# me433_2017.net
KiCad netlist of a schematic drawn in EAGLE
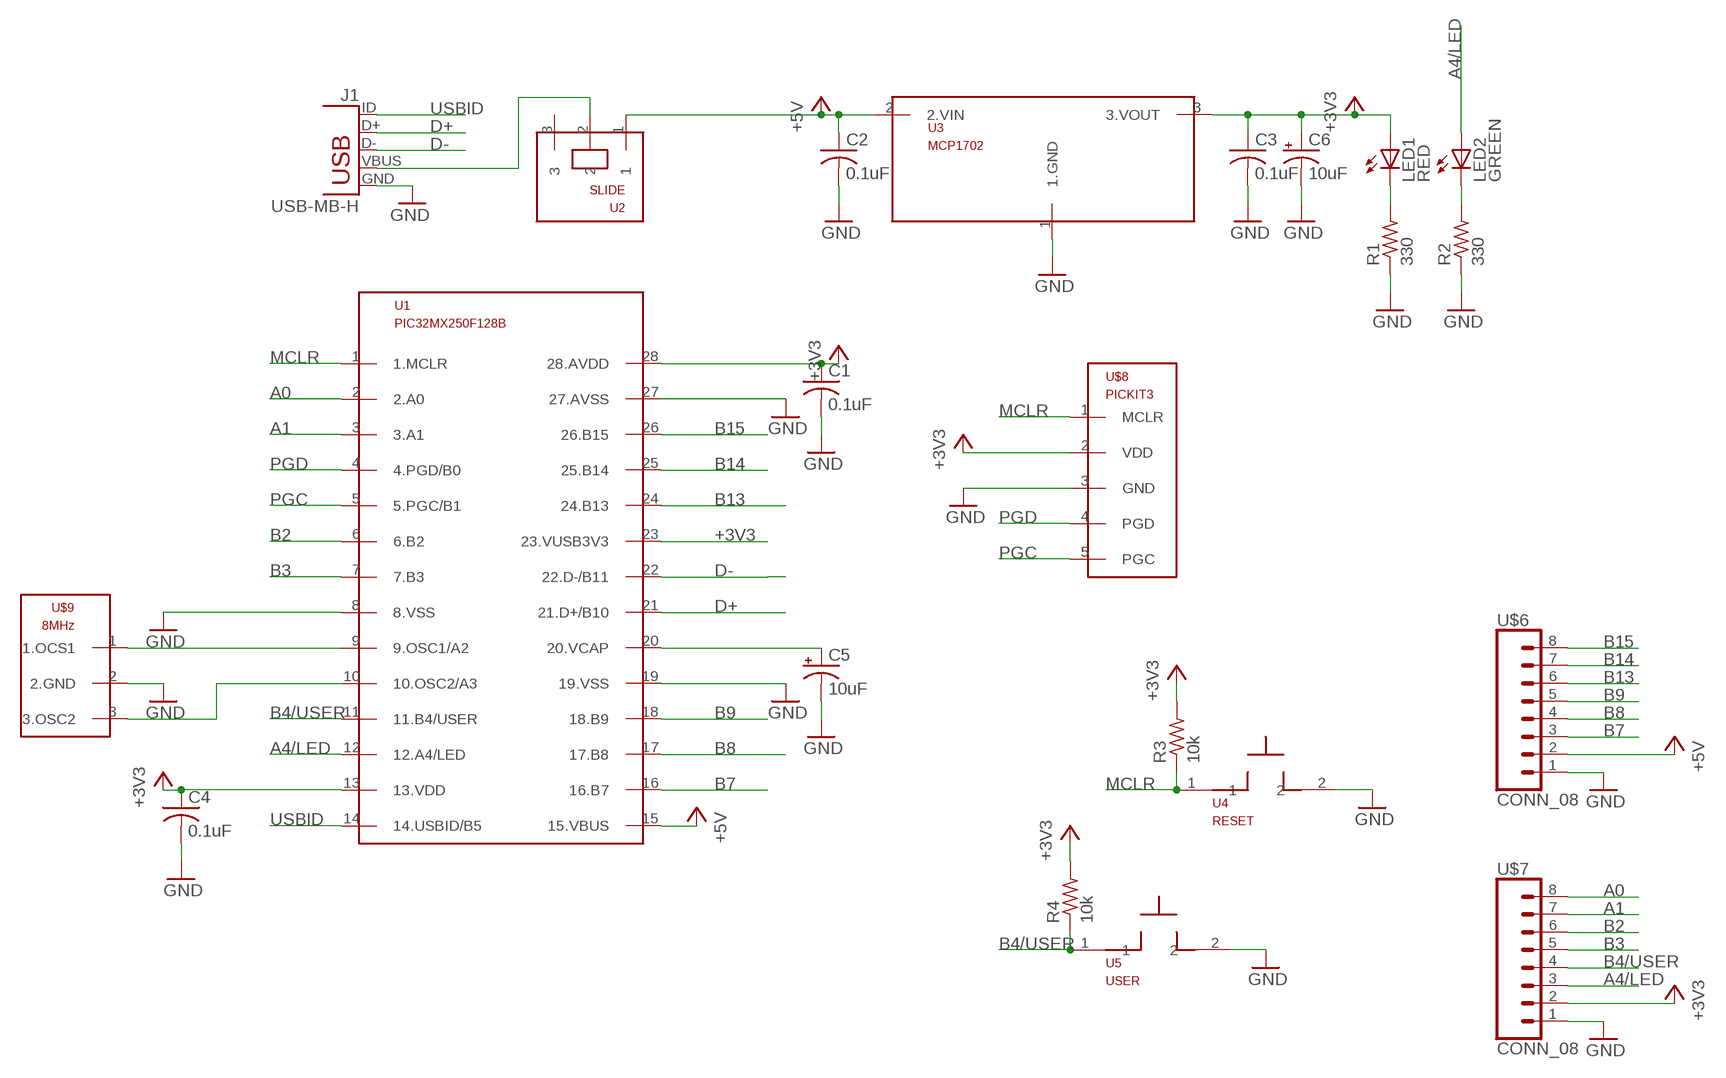
[diagram p0: schematic, sheet 1]

(export (version "E")
  (design (tool "Eeschema 10.0.6"))
  (components
    (comp (ref "C1")
      (value "0.1uF")
      (footprint "eagle-import:C025-025X050")
      (libsource (lib "eagle-import") (part "C-US025-025X050"))
    )
    (comp (ref "C2")
      (value "0.1uF")
      (footprint "eagle-import:C025-025X050")
      (libsource (lib "eagle-import") (part "C-US025-025X050"))
    )
    (comp (ref "C3")
      (value "0.1uF")
      (footprint "eagle-import:C025-025X050")
      (libsource (lib "eagle-import") (part "C-US025-025X050"))
    )
    (comp (ref "C4")
      (value "0.1uF")
      (footprint "eagle-import:C025-025X050")
      (libsource (lib "eagle-import") (part "C-US025-025X050"))
    )
    (comp (ref "C5")
      (value "10uF")
      (footprint "eagle-import:B45181B")
      (libsource (lib "eagle-import") (part "CPOL-USB45181B"))
    )
    (comp (ref "C6")
      (value "10uF")
      (footprint "eagle-import:B45181B")
      (libsource (lib "eagle-import") (part "CPOL-USB45181B"))
    )
    (comp (ref "J1")
      (value "USB-MB-H")
      (footprint "eagle-import:USB-MB-H")
      (libsource (lib "eagle-import") (part "USB-MB-H"))
    )
    (comp (ref "LED1")
      (value "RED")
      (footprint "eagle-import:LED3MM")
      (libsource (lib "eagle-import") (part "LED3MM"))
    )
    (comp (ref "LED2")
      (value "GREEN")
      (footprint "eagle-import:LED3MM")
      (libsource (lib "eagle-import") (part "LED3MM"))
    )
    (comp (ref "R1")
      (value "330")
      (footprint "eagle-import:0207_10")
      (libsource (lib "eagle-import") (part "R-US_0207/10"))
    )
    (comp (ref "R2")
      (value "330")
      (footprint "eagle-import:0207_10")
      (libsource (lib "eagle-import") (part "R-US_0207/10"))
    )
    (comp (ref "R3")
      (value "10k")
      (footprint "eagle-import:0207_10")
      (libsource (lib "eagle-import") (part "R-US_0207/10"))
    )
    (comp (ref "R4")
      (value "10k")
      (footprint "eagle-import:0207_10")
      (libsource (lib "eagle-import") (part "R-US_0207/10"))
    )
    (comp (ref "U$6")
      (value "CONN_08")
      (footprint "eagle-import:1X08")
      (libsource (lib "eagle-import") (part "CONN_08"))
    )
    (comp (ref "U$7")
      (value "CONN_08")
      (footprint "eagle-import:1X08")
      (libsource (lib "eagle-import") (part "CONN_08"))
    )
    (comp (ref "U$8")
      (value "PICKIT3")
      (footprint "eagle-import:1X05")
      (libsource (lib "eagle-import") (part "PICKIT3"))
    )
    (comp (ref "U$9")
      (value "8MHz")
      (footprint "eagle-import:OSC")
      (libsource (lib "eagle-import") (part "OSC"))
    )
    (comp (ref "U1")
      (value "PIC32MX250F128B")
      (footprint "eagle-import:DIL28-3")
      (libsource (lib "eagle-import") (part "PIC32MX250F128B"))
    )
    (comp (ref "U2")
      (value "SLIDE")
      (footprint "eagle-import:SLIDE")
      (libsource (lib "eagle-import") (part "SLIDE"))
    )
    (comp (ref "U3")
      (value "MCP1702")
      (footprint "eagle-import:TO92")
      (libsource (lib "eagle-import") (part "MCP1702"))
    )
    (comp (ref "U4")
      (value "RESET")
      (footprint "eagle-import:PB")
      (libsource (lib "eagle-import") (part "PB"))
    )
    (comp (ref "U5")
      (value "USER")
      (footprint "eagle-import:PB")
      (libsource (lib "eagle-import") (part "PB"))
    )
  )
  (nets
    (net (code "1") (name "+3V3") (class "Default")
      (node (ref "C1") (pin "1") (pinfunction "1_1") (pintype "passive"))
      (node (ref "C3") (pin "1") (pinfunction "1_1") (pintype "passive"))
      (node (ref "C4") (pin "1") (pinfunction "1_1") (pintype "passive"))
      (node (ref "C6") (pin "+") (pinfunction "+_+") (pintype "passive"))
      (node (ref "LED1") (pin "A") (pinfunction "A_A") (pintype "passive"))
      (node (ref "R3") (pin "2") (pinfunction "2_2") (pintype "passive"))
      (node (ref "R4") (pin "2") (pinfunction "2_2") (pintype "passive"))
      (node (ref "U$7") (pin "2") (pinfunction "2_2") (pintype "passive"))
      (node (ref "U$8") (pin "2") (pinfunction "VDD_2") (pintype "bidirectional"))
      (node (ref "U1") (pin "13") (pinfunction "13.VDD_13") (pintype "bidirectional"))
      (node (ref "U1") (pin "23") (pinfunction "23.VUSB3V3_23") (pintype "bidirectional"))
      (node (ref "U1") (pin "28") (pinfunction "28.AVDD_28") (pintype "bidirectional"))
      (node (ref "U3") (pin "3") (pinfunction "3.VOUT_3") (pintype "bidirectional"))
    )
    (net (code "2") (name "+5V") (class "Default")
      (node (ref "C2") (pin "1") (pinfunction "1_1") (pintype "passive"))
      (node (ref "U$6") (pin "2") (pinfunction "2_2") (pintype "passive"))
      (node (ref "U1") (pin "15") (pinfunction "15.VBUS_15") (pintype "bidirectional"))
      (node (ref "U2") (pin "1") (pinfunction "1_1") (pintype "bidirectional"))
      (node (ref "U3") (pin "2") (pinfunction "2.VIN_2") (pintype "bidirectional"))
    )
    (net (code "3") (name "/A0") (class "Default")
      (node (ref "U$7") (pin "8") (pinfunction "8_8") (pintype "passive"))
      (node (ref "U1") (pin "2") (pinfunction "2.A0_2") (pintype "bidirectional"))
    )
    (net (code "4") (name "/A1") (class "Default")
      (node (ref "U$7") (pin "7") (pinfunction "7_7") (pintype "passive"))
      (node (ref "U1") (pin "3") (pinfunction "3.A1_3") (pintype "bidirectional"))
    )
    (net (code "5") (name "/A4{slash}LED") (class "Default")
      (node (ref "LED2") (pin "A") (pinfunction "A_A") (pintype "passive"))
      (node (ref "U$7") (pin "3") (pinfunction "3_3") (pintype "passive"))
      (node (ref "U1") (pin "12") (pinfunction "12.A4/LED_12") (pintype "bidirectional"))
    )
    (net (code "6") (name "/B2") (class "Default")
      (node (ref "U$7") (pin "6") (pinfunction "6_6") (pintype "passive"))
      (node (ref "U1") (pin "6") (pinfunction "6.B2_6") (pintype "bidirectional"))
    )
    (net (code "7") (name "/B3") (class "Default")
      (node (ref "U$7") (pin "5") (pinfunction "5_5") (pintype "passive"))
      (node (ref "U1") (pin "7") (pinfunction "7.B3_7") (pintype "bidirectional"))
    )
    (net (code "8") (name "/B4{slash}USER") (class "Default")
      (node (ref "R4") (pin "1") (pinfunction "1_1") (pintype "passive"))
      (node (ref "U$7") (pin "4") (pinfunction "4_4") (pintype "passive"))
      (node (ref "U1") (pin "11") (pinfunction "11.B4/USER_11") (pintype "bidirectional"))
      (node (ref "U5") (pin "1") (pinfunction "1_1") (pintype "bidirectional"))
    )
    (net (code "9") (name "/B7") (class "Default")
      (node (ref "U$6") (pin "3") (pinfunction "3_3") (pintype "passive"))
      (node (ref "U1") (pin "16") (pinfunction "16.B7_16") (pintype "bidirectional"))
    )
    (net (code "10") (name "/B8") (class "Default")
      (node (ref "U$6") (pin "4") (pinfunction "4_4") (pintype "passive"))
      (node (ref "U1") (pin "17") (pinfunction "17.B8_17") (pintype "bidirectional"))
    )
    (net (code "11") (name "/B9") (class "Default")
      (node (ref "U$6") (pin "5") (pinfunction "5_5") (pintype "passive"))
      (node (ref "U1") (pin "18") (pinfunction "18.B9_18") (pintype "bidirectional"))
    )
    (net (code "12") (name "/B13") (class "Default")
      (node (ref "U$6") (pin "6") (pinfunction "6_6") (pintype "passive"))
      (node (ref "U1") (pin "24") (pinfunction "24.B13_24") (pintype "bidirectional"))
    )
    (net (code "13") (name "/B14") (class "Default")
      (node (ref "U$6") (pin "7") (pinfunction "7_7") (pintype "passive"))
      (node (ref "U1") (pin "25") (pinfunction "25.B14_25") (pintype "bidirectional"))
    )
    (net (code "14") (name "/B15") (class "Default")
      (node (ref "U$6") (pin "8") (pinfunction "8_8") (pintype "passive"))
      (node (ref "U1") (pin "26") (pinfunction "26.B15_26") (pintype "bidirectional"))
    )
    (net (code "15") (name "/D+") (class "Default")
      (node (ref "J1") (pin "D+") (pinfunction "D+_D+") (pintype "bidirectional"))
      (node (ref "U1") (pin "21") (pinfunction "21.D+/B10_21") (pintype "bidirectional"))
    )
    (net (code "16") (name "/D-") (class "Default")
      (node (ref "J1") (pin "D-") (pinfunction "D-_D-") (pintype "bidirectional"))
      (node (ref "U1") (pin "22") (pinfunction "22.D-/B11_22") (pintype "bidirectional"))
    )
    (net (code "17") (name "/MCLR") (class "Default")
      (node (ref "R3") (pin "1") (pinfunction "1_1") (pintype "passive"))
      (node (ref "U$8") (pin "1") (pinfunction "MCLR_1") (pintype "bidirectional"))
      (node (ref "U1") (pin "1") (pinfunction "1.MCLR_1") (pintype "bidirectional"))
      (node (ref "U4") (pin "1") (pinfunction "1_1") (pintype "bidirectional"))
    )
    (net (code "18") (name "/PGC") (class "Default")
      (node (ref "U$8") (pin "5") (pinfunction "PGC_5") (pintype "bidirectional"))
      (node (ref "U1") (pin "5") (pinfunction "5.PGC/B1_5") (pintype "bidirectional"))
    )
    (net (code "19") (name "/PGD") (class "Default")
      (node (ref "U$8") (pin "4") (pinfunction "PGD_4") (pintype "bidirectional"))
      (node (ref "U1") (pin "4") (pinfunction "4.PGD/B0_4") (pintype "bidirectional"))
    )
    (net (code "20") (name "/USBID") (class "Default")
      (node (ref "J1") (pin "ID") (pinfunction "ID_ID") (pintype "bidirectional"))
      (node (ref "U1") (pin "14") (pinfunction "14.USBID/B5_14") (pintype "bidirectional"))
    )
    (net (code "21") (name "GND") (class "Default")
      (node (ref "C1") (pin "2") (pinfunction "2_2") (pintype "passive"))
      (node (ref "C2") (pin "2") (pinfunction "2_2") (pintype "passive"))
      (node (ref "C3") (pin "2") (pinfunction "2_2") (pintype "passive"))
      (node (ref "C4") (pin "2") (pinfunction "2_2") (pintype "passive"))
      (node (ref "C5") (pin "-") (pinfunction "-_-") (pintype "passive"))
      (node (ref "C6") (pin "-") (pinfunction "-_-") (pintype "passive"))
      (node (ref "J1") (pin "GND") (pinfunction "GND_GND") (pintype "bidirectional"))
      (node (ref "R1") (pin "1") (pinfunction "1_1") (pintype "passive"))
      (node (ref "R2") (pin "1") (pinfunction "1_1") (pintype "passive"))
      (node (ref "U$6") (pin "1") (pinfunction "1_1") (pintype "passive"))
      (node (ref "U$7") (pin "1") (pinfunction "1_1") (pintype "passive"))
      (node (ref "U$8") (pin "3") (pinfunction "GND_3") (pintype "bidirectional"))
      (node (ref "U$9") (pin "2") (pinfunction "2.GND_2") (pintype "bidirectional"))
      (node (ref "U1") (pin "19") (pinfunction "19.VSS_19") (pintype "bidirectional"))
      (node (ref "U1") (pin "27") (pinfunction "27.AVSS_27") (pintype "bidirectional"))
      (node (ref "U1") (pin "8") (pinfunction "8.VSS_8") (pintype "bidirectional"))
      (node (ref "U3") (pin "1") (pinfunction "1.GND_1") (pintype "bidirectional"))
      (node (ref "U4") (pin "2") (pinfunction "2_2") (pintype "bidirectional"))
      (node (ref "U5") (pin "2") (pinfunction "2_2") (pintype "bidirectional"))
    )
    (net (code "22") (name "Net-(J1-PadVBUS)") (class "Default")
      (node (ref "J1") (pin "VBUS") (pinfunction "VBUS_VBUS") (pintype "bidirectional"))
      (node (ref "U2") (pin "2") (pinfunction "2_2") (pintype "bidirectional"))
    )
    (net (code "23") (name "Net-(LED1-C)") (class "Default")
      (node (ref "LED1") (pin "K") (pinfunction "C_K") (pintype "passive"))
      (node (ref "R1") (pin "2") (pinfunction "2_2") (pintype "passive"))
    )
    (net (code "24") (name "Net-(LED2-C)") (class "Default")
      (node (ref "LED2") (pin "K") (pinfunction "C_K") (pintype "passive"))
      (node (ref "R2") (pin "2") (pinfunction "2_2") (pintype "passive"))
    )
    (net (code "25") (name "Net-(U$9-1.OCS1)") (class "Default")
      (node (ref "U$9") (pin "1") (pinfunction "1.OCS1_1") (pintype "bidirectional"))
      (node (ref "U1") (pin "9") (pinfunction "9.OSC1/A2_9") (pintype "bidirectional"))
    )
    (net (code "26") (name "Net-(U$9-3.OSC2)") (class "Default")
      (node (ref "U$9") (pin "3") (pinfunction "3.OSC2_3") (pintype "bidirectional"))
      (node (ref "U1") (pin "10") (pinfunction "10.OSC2/A3_10") (pintype "bidirectional"))
    )
    (net (code "27") (name "Net-(U1-20.VCAP)") (class "Default")
      (node (ref "C5") (pin "+") (pinfunction "+_+") (pintype "passive"))
      (node (ref "U1") (pin "20") (pinfunction "20.VCAP_20") (pintype "bidirectional"))
    )
    (net (code "28") (name "unconnected-(U2-Pad3)") (class "Default")
      (node (ref "U2") (pin "3") (pinfunction "3_3") (pintype "bidirectional"))
    )
  )
)
